# Pratica_01.net
KiCad netlist of a schematic drawn in EasyEDA
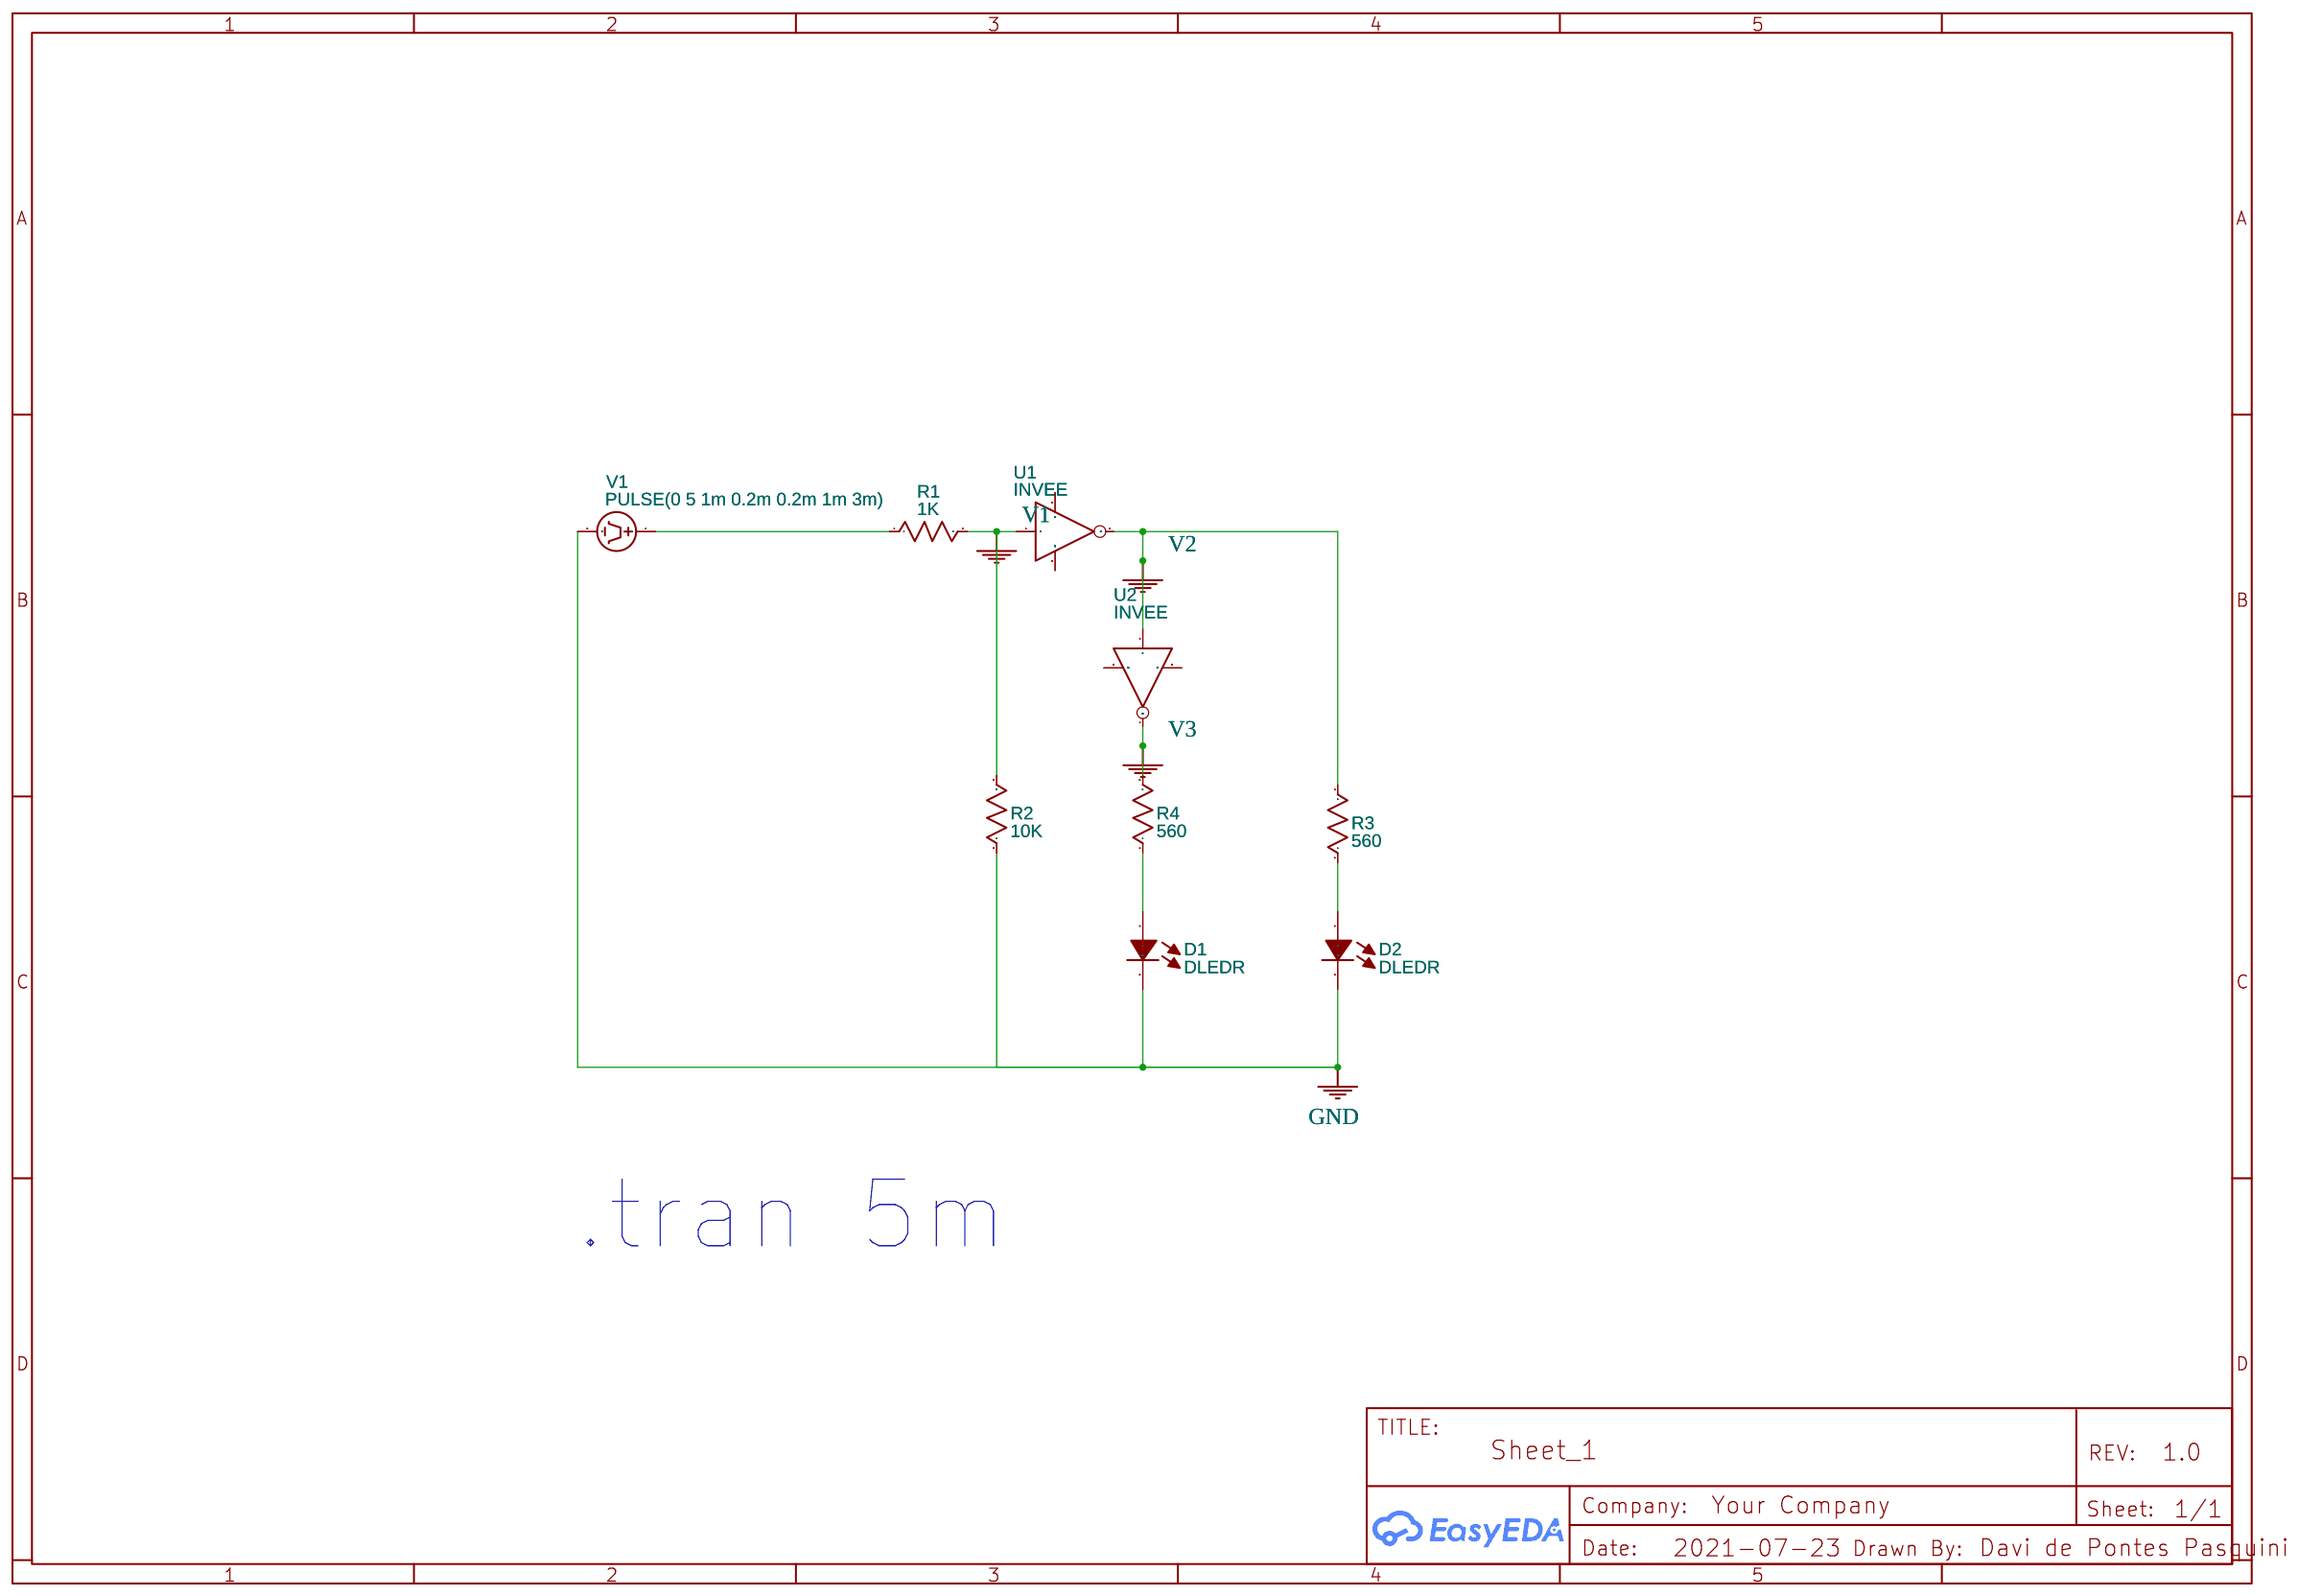
[diagram p0: schematic sheet]

(export (version "E")
  (design (tool "Eeschema 10.0.6"))
  (components
    (comp (ref "D1") (value "DLEDR") (libsource (lib "") (part "DLEDR")))
    (comp (ref "D2") (value "DLEDR") (libsource (lib "") (part "DLEDR")))
    (comp (ref "R1") (value "1K") (libsource (lib "") (part "Resistor_US_1")))
    (comp (ref "R2") (value "10K") (libsource (lib "") (part "Resistor_US")))
    (comp (ref "R3") (value "560") (libsource (lib "") (part "Resistor_US")))
    (comp (ref "R4") (value "560") (libsource (lib "") (part "Resistor_US")))
    (comp (ref "U1") (value "INVEE") (libsource (lib "") (part "LOGIC_1")))
    (comp (ref "U2") (value "INVEE") (libsource (lib "") (part "LOGIC")))
    (comp (ref "V1") (value "PULSE(0 5 1m 0.2m 0.2m 1m 3m)") (libsource (lib "") (part "VPULSE")))
  )
  (nets
    (net (code "1") (name "GND") (class "Default")
      (node (ref "D1") (pin "2") (pinfunction "C_2") (pintype "unspecified"))
      (node (ref "D2") (pin "2") (pinfunction "C_2") (pintype "unspecified"))
      (node (ref "R2") (pin "1") (pinfunction "1_1") (pintype "unspecified"))
      (node (ref "V1") (pin "2") (pinfunction "2_2") (pintype "unspecified"))
    )
    (net (code "2") (name "Net-(D1-A)") (class "Default")
      (node (ref "D1") (pin "1") (pinfunction "A_1") (pintype "unspecified"))
      (node (ref "R4") (pin "1") (pinfunction "1_1") (pintype "unspecified"))
    )
    (net (code "3") (name "Net-(D2-A)") (class "Default")
      (node (ref "D2") (pin "1") (pinfunction "A_1") (pintype "unspecified"))
      (node (ref "R3") (pin "1") (pinfunction "1_1") (pintype "unspecified"))
    )
    (net (code "4") (name "Net-(R1-Pad1)") (class "Default")
      (node (ref "R1") (pin "1") (pinfunction "1_1") (pintype "unspecified"))
      (node (ref "V1") (pin "1") (pinfunction "1_1") (pintype "unspecified"))
    )
    (net (code "5") (name "V1") (class "Default")
      (node (ref "R1") (pin "2") (pinfunction "2_2") (pintype "unspecified"))
      (node (ref "R2") (pin "2") (pinfunction "2_2") (pintype "unspecified"))
      (node (ref "U1") (pin "1") (pinfunction "IN_1") (pintype "input"))
    )
    (net (code "6") (name "V2") (class "Default")
      (node (ref "R3") (pin "2") (pinfunction "2_2") (pintype "unspecified"))
      (node (ref "U1") (pin "4") (pinfunction "OUT_4") (pintype "output"))
      (node (ref "U2") (pin "1") (pinfunction "IN_1") (pintype "input"))
    )
    (net (code "7") (name "V3") (class "Default")
      (node (ref "R4") (pin "2") (pinfunction "2_2") (pintype "unspecified"))
      (node (ref "U2") (pin "4") (pinfunction "OUT_4") (pintype "output"))
    )
    (net (code "8") (name "unconnected-(U1-GND-Pad3)") (class "Default")
      (node (ref "U1") (pin "3") (pinfunction "GND_3") (pintype "passive"))
    )
    (net (code "9") (name "unconnected-(U1-VDD-Pad2)") (class "Default")
      (node (ref "U1") (pin "2") (pinfunction "VDD_2") (pintype "passive"))
    )
    (net (code "10") (name "unconnected-(U2-GND-Pad3)") (class "Default")
      (node (ref "U2") (pin "3") (pinfunction "GND_3") (pintype "passive"))
    )
    (net (code "11") (name "unconnected-(U2-VDD-Pad2)") (class "Default")
      (node (ref "U2") (pin "2") (pinfunction "VDD_2") (pintype "passive"))
    )
  )
)
